# breakoutModule.net
KiCad netlist of a schematic drawn in EAGLE
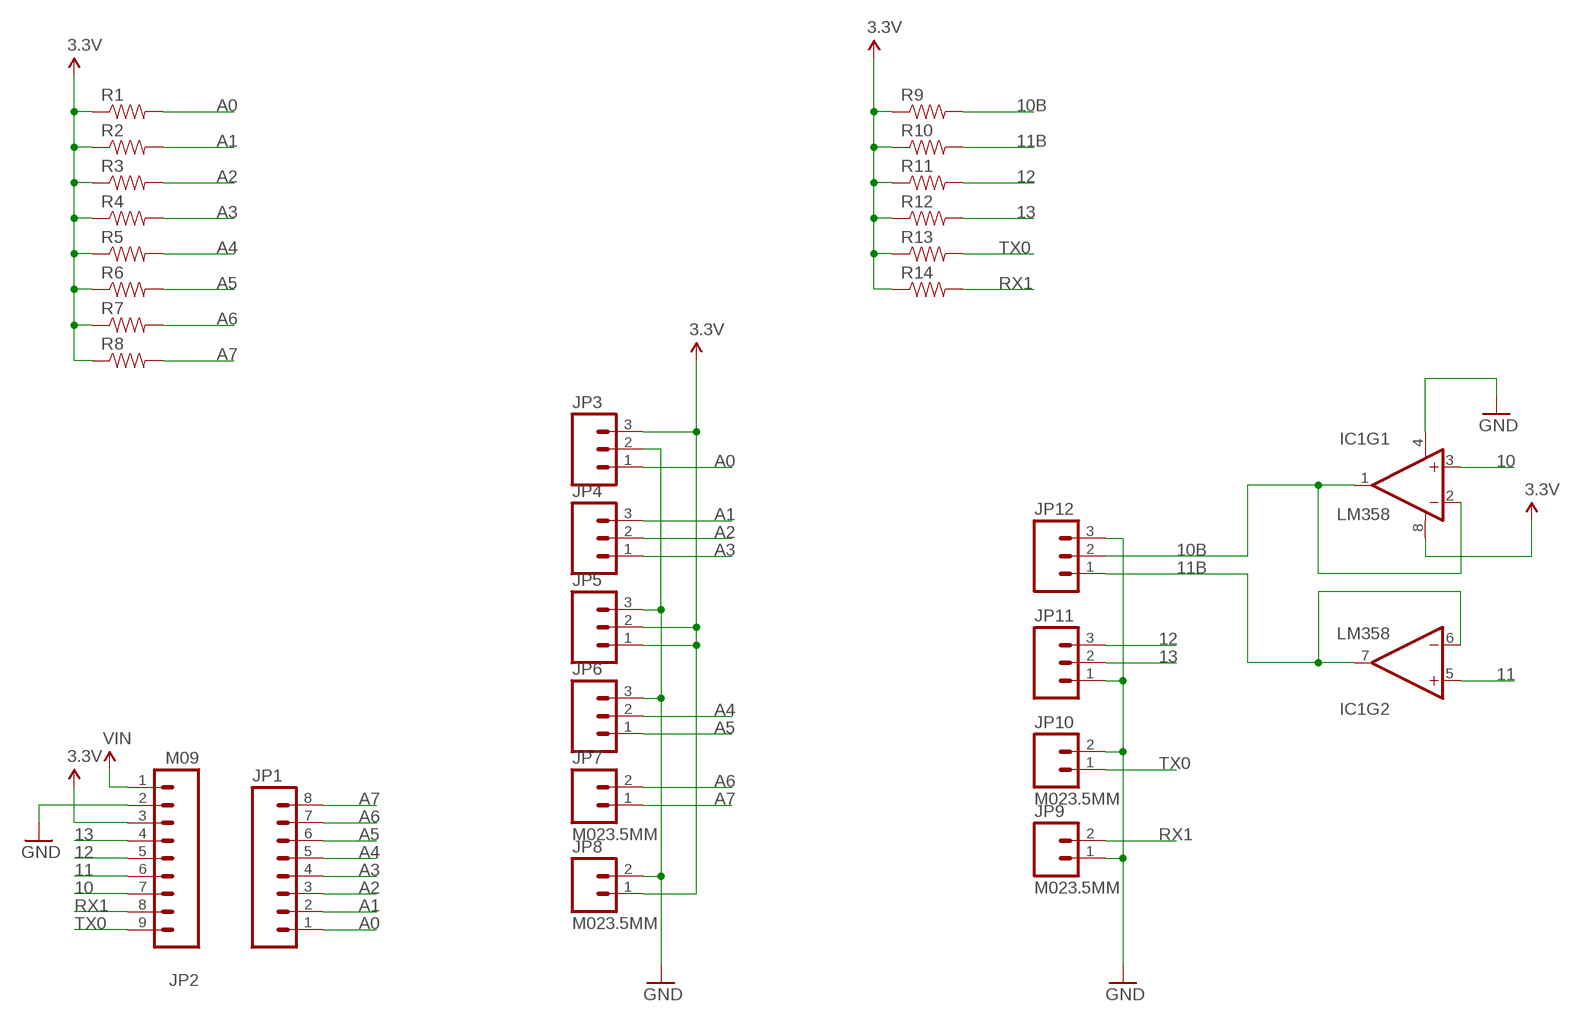
[diagram p0: schematic, sheet 1]

(export (version "E")
  (design (tool "Eeschema 10.0.6"))
  (components
    (comp (ref "IC1")
      (value "LM358")
      (footprint "eagle-import:DIP08")
      (libsource (lib "eagle-import") (part "LM358"))
    )
    (comp (ref "JP1")
      (value "M081X08")
      (footprint "eagle-import:1X08")
      (libsource (lib "eagle-import") (part "M081X08"))
    )
    (comp (ref "JP2")
      (value "M09")
      (footprint "eagle-import:1X09")
      (libsource (lib "eagle-import") (part "M09"))
    )
    (comp (ref "JP3")
      (value "M03SCREW")
      (footprint "eagle-import:SCREWTERMINAL-3.5MM-3")
      (libsource (lib "eagle-import") (part "M03SCREW"))
    )
    (comp (ref "JP4")
      (value "M03SCREW")
      (footprint "eagle-import:SCREWTERMINAL-3.5MM-3")
      (libsource (lib "eagle-import") (part "M03SCREW"))
    )
    (comp (ref "JP5")
      (value "M03SCREW")
      (footprint "eagle-import:SCREWTERMINAL-3.5MM-3")
      (libsource (lib "eagle-import") (part "M03SCREW"))
    )
    (comp (ref "JP6")
      (value "M03SCREW")
      (footprint "eagle-import:SCREWTERMINAL-3.5MM-3")
      (libsource (lib "eagle-import") (part "M03SCREW"))
    )
    (comp (ref "JP7")
      (value "M023.5MM")
      (footprint "eagle-import:SCREWTERMINAL-3.5MM-2")
      (libsource (lib "eagle-import") (part "M023.5MM"))
    )
    (comp (ref "JP8")
      (value "M023.5MM")
      (footprint "eagle-import:SCREWTERMINAL-3.5MM-2")
      (libsource (lib "eagle-import") (part "M023.5MM"))
    )
    (comp (ref "JP9")
      (value "M023.5MM")
      (footprint "eagle-import:SCREWTERMINAL-3.5MM-2")
      (libsource (lib "eagle-import") (part "M023.5MM"))
    )
    (comp (ref "JP10")
      (value "M023.5MM")
      (footprint "eagle-import:SCREWTERMINAL-3.5MM-2")
      (libsource (lib "eagle-import") (part "M023.5MM"))
    )
    (comp (ref "JP11")
      (value "M03SCREW")
      (footprint "eagle-import:SCREWTERMINAL-3.5MM-3")
      (libsource (lib "eagle-import") (part "M03SCREW"))
    )
    (comp (ref "JP12")
      (value "M03SCREW")
      (footprint "eagle-import:SCREWTERMINAL-3.5MM-3")
      (libsource (lib "eagle-import") (part "M03SCREW"))
    )
    (comp (ref "R1")
      (value "RESISTOR1206")
      (footprint "eagle-import:1206")
      (libsource (lib "eagle-import") (part "RESISTOR1206"))
    )
    (comp (ref "R2")
      (value "RESISTOR1206")
      (footprint "eagle-import:1206")
      (libsource (lib "eagle-import") (part "RESISTOR1206"))
    )
    (comp (ref "R3")
      (value "RESISTOR1206")
      (footprint "eagle-import:1206")
      (libsource (lib "eagle-import") (part "RESISTOR1206"))
    )
    (comp (ref "R4")
      (value "RESISTOR1206")
      (footprint "eagle-import:1206")
      (libsource (lib "eagle-import") (part "RESISTOR1206"))
    )
    (comp (ref "R5")
      (value "RESISTOR1206")
      (footprint "eagle-import:1206")
      (libsource (lib "eagle-import") (part "RESISTOR1206"))
    )
    (comp (ref "R6")
      (value "RESISTOR1206")
      (footprint "eagle-import:1206")
      (libsource (lib "eagle-import") (part "RESISTOR1206"))
    )
    (comp (ref "R7")
      (value "RESISTOR1206")
      (footprint "eagle-import:1206")
      (libsource (lib "eagle-import") (part "RESISTOR1206"))
    )
    (comp (ref "R8")
      (value "RESISTOR1206")
      (footprint "eagle-import:1206")
      (libsource (lib "eagle-import") (part "RESISTOR1206"))
    )
    (comp (ref "R9")
      (value "RESISTOR1206")
      (footprint "eagle-import:1206")
      (libsource (lib "eagle-import") (part "RESISTOR1206"))
    )
    (comp (ref "R10")
      (value "RESISTOR1206")
      (footprint "eagle-import:1206")
      (libsource (lib "eagle-import") (part "RESISTOR1206"))
    )
    (comp (ref "R11")
      (value "RESISTOR1206")
      (footprint "eagle-import:1206")
      (libsource (lib "eagle-import") (part "RESISTOR1206"))
    )
    (comp (ref "R12")
      (value "RESISTOR1206")
      (footprint "eagle-import:1206")
      (libsource (lib "eagle-import") (part "RESISTOR1206"))
    )
    (comp (ref "R13")
      (value "RESISTOR1206")
      (footprint "eagle-import:1206")
      (libsource (lib "eagle-import") (part "RESISTOR1206"))
    )
    (comp (ref "R14")
      (value "RESISTOR1206")
      (footprint "eagle-import:1206")
      (libsource (lib "eagle-import") (part "RESISTOR1206"))
    )
  )
  (nets
    (net (code "1") (name "/10") (class "Default")
      (node (ref "IC1") (pin "3") (pinfunction "+IN_3") (pintype "input"))
      (node (ref "JP2") (pin "7") (pinfunction "7_7") (pintype "passive"))
    )
    (net (code "2") (name "/10B") (class "Default")
      (node (ref "IC1") (pin "1") (pinfunction "OUT_1") (pintype "output"))
      (node (ref "IC1") (pin "2") (pinfunction "-IN_2") (pintype "input"))
      (node (ref "JP12") (pin "2") (pinfunction "2_2") (pintype "passive"))
      (node (ref "R9") (pin "2") (pinfunction "2_2") (pintype "passive"))
    )
    (net (code "3") (name "/11") (class "Default")
      (node (ref "IC1") (pin "5") (pinfunction "+IN_5") (pintype "input"))
      (node (ref "JP2") (pin "6") (pinfunction "6_6") (pintype "passive"))
    )
    (net (code "4") (name "/11B") (class "Default")
      (node (ref "IC1") (pin "6") (pinfunction "-IN_6") (pintype "input"))
      (node (ref "IC1") (pin "7") (pinfunction "OUT_7") (pintype "output"))
      (node (ref "JP12") (pin "1") (pinfunction "1_1") (pintype "passive"))
      (node (ref "R10") (pin "2") (pinfunction "2_2") (pintype "passive"))
    )
    (net (code "5") (name "/12") (class "Default")
      (node (ref "JP11") (pin "3") (pinfunction "3_3") (pintype "passive"))
      (node (ref "JP2") (pin "5") (pinfunction "5_5") (pintype "passive"))
      (node (ref "R11") (pin "2") (pinfunction "2_2") (pintype "passive"))
    )
    (net (code "6") (name "/13") (class "Default")
      (node (ref "JP11") (pin "2") (pinfunction "2_2") (pintype "passive"))
      (node (ref "JP2") (pin "4") (pinfunction "4_4") (pintype "passive"))
      (node (ref "R12") (pin "2") (pinfunction "2_2") (pintype "passive"))
    )
    (net (code "7") (name "/A0") (class "Default")
      (node (ref "JP1") (pin "1") (pinfunction "1_1") (pintype "passive"))
      (node (ref "JP3") (pin "1") (pinfunction "1_1") (pintype "passive"))
      (node (ref "R1") (pin "2") (pinfunction "2_2") (pintype "passive"))
    )
    (net (code "8") (name "/A1") (class "Default")
      (node (ref "JP1") (pin "2") (pinfunction "2_2") (pintype "passive"))
      (node (ref "JP4") (pin "3") (pinfunction "3_3") (pintype "passive"))
      (node (ref "R2") (pin "2") (pinfunction "2_2") (pintype "passive"))
    )
    (net (code "9") (name "/A2") (class "Default")
      (node (ref "JP1") (pin "3") (pinfunction "3_3") (pintype "passive"))
      (node (ref "JP4") (pin "2") (pinfunction "2_2") (pintype "passive"))
      (node (ref "R3") (pin "2") (pinfunction "2_2") (pintype "passive"))
    )
    (net (code "10") (name "/A3") (class "Default")
      (node (ref "JP1") (pin "4") (pinfunction "4_4") (pintype "passive"))
      (node (ref "JP4") (pin "1") (pinfunction "1_1") (pintype "passive"))
      (node (ref "R4") (pin "2") (pinfunction "2_2") (pintype "passive"))
    )
    (net (code "11") (name "/A4") (class "Default")
      (node (ref "JP1") (pin "5") (pinfunction "5_5") (pintype "passive"))
      (node (ref "JP6") (pin "2") (pinfunction "2_2") (pintype "passive"))
      (node (ref "R5") (pin "2") (pinfunction "2_2") (pintype "passive"))
    )
    (net (code "12") (name "/A5") (class "Default")
      (node (ref "JP1") (pin "6") (pinfunction "6_6") (pintype "passive"))
      (node (ref "JP6") (pin "1") (pinfunction "1_1") (pintype "passive"))
      (node (ref "R6") (pin "2") (pinfunction "2_2") (pintype "passive"))
    )
    (net (code "13") (name "/A6") (class "Default")
      (node (ref "JP1") (pin "7") (pinfunction "7_7") (pintype "passive"))
      (node (ref "JP7") (pin "2") (pinfunction "2_2") (pintype "passive"))
      (node (ref "R7") (pin "2") (pinfunction "2_2") (pintype "passive"))
    )
    (net (code "14") (name "/A7") (class "Default")
      (node (ref "JP1") (pin "8") (pinfunction "8_8") (pintype "passive"))
      (node (ref "JP7") (pin "1") (pinfunction "1_1") (pintype "passive"))
      (node (ref "R8") (pin "2") (pinfunction "2_2") (pintype "passive"))
    )
    (net (code "15") (name "/RX1") (class "Default")
      (node (ref "JP2") (pin "8") (pinfunction "8_8") (pintype "passive"))
      (node (ref "JP9") (pin "2") (pinfunction "2_2") (pintype "passive"))
      (node (ref "R14") (pin "2") (pinfunction "2_2") (pintype "passive"))
    )
    (net (code "16") (name "/TX0") (class "Default")
      (node (ref "JP10") (pin "1") (pinfunction "1_1") (pintype "passive"))
      (node (ref "JP2") (pin "9") (pinfunction "9_9") (pintype "passive"))
      (node (ref "R13") (pin "2") (pinfunction "2_2") (pintype "passive"))
    )
    (net (code "17") (name "3.3V") (class "Default")
      (node (ref "IC1") (pin "8") (pinfunction "V+_8") (pintype "power_in"))
      (node (ref "JP2") (pin "3") (pinfunction "3_3") (pintype "passive"))
      (node (ref "JP3") (pin "3") (pinfunction "3_3") (pintype "passive"))
      (node (ref "JP5") (pin "1") (pinfunction "1_1") (pintype "passive"))
      (node (ref "JP5") (pin "2") (pinfunction "2_2") (pintype "passive"))
      (node (ref "JP8") (pin "1") (pinfunction "1_1") (pintype "passive"))
      (node (ref "R1") (pin "1") (pinfunction "1_1") (pintype "passive"))
      (node (ref "R10") (pin "1") (pinfunction "1_1") (pintype "passive"))
      (node (ref "R11") (pin "1") (pinfunction "1_1") (pintype "passive"))
      (node (ref "R12") (pin "1") (pinfunction "1_1") (pintype "passive"))
      (node (ref "R13") (pin "1") (pinfunction "1_1") (pintype "passive"))
      (node (ref "R14") (pin "1") (pinfunction "1_1") (pintype "passive"))
      (node (ref "R2") (pin "1") (pinfunction "1_1") (pintype "passive"))
      (node (ref "R3") (pin "1") (pinfunction "1_1") (pintype "passive"))
      (node (ref "R4") (pin "1") (pinfunction "1_1") (pintype "passive"))
      (node (ref "R5") (pin "1") (pinfunction "1_1") (pintype "passive"))
      (node (ref "R6") (pin "1") (pinfunction "1_1") (pintype "passive"))
      (node (ref "R7") (pin "1") (pinfunction "1_1") (pintype "passive"))
      (node (ref "R8") (pin "1") (pinfunction "1_1") (pintype "passive"))
      (node (ref "R9") (pin "1") (pinfunction "1_1") (pintype "passive"))
    )
    (net (code "18") (name "GND") (class "Default")
      (node (ref "IC1") (pin "4") (pinfunction "V-_4") (pintype "power_in"))
      (node (ref "JP10") (pin "2") (pinfunction "2_2") (pintype "passive"))
      (node (ref "JP11") (pin "1") (pinfunction "1_1") (pintype "passive"))
      (node (ref "JP12") (pin "3") (pinfunction "3_3") (pintype "passive"))
      (node (ref "JP2") (pin "2") (pinfunction "2_2") (pintype "passive"))
      (node (ref "JP3") (pin "2") (pinfunction "2_2") (pintype "passive"))
      (node (ref "JP5") (pin "3") (pinfunction "3_3") (pintype "passive"))
      (node (ref "JP6") (pin "3") (pinfunction "3_3") (pintype "passive"))
      (node (ref "JP8") (pin "2") (pinfunction "2_2") (pintype "passive"))
      (node (ref "JP9") (pin "1") (pinfunction "1_1") (pintype "passive"))
    )
    (net (code "19") (name "VIN") (class "Default")
      (node (ref "JP2") (pin "1") (pinfunction "1_1") (pintype "passive"))
    )
  )
)
